# schematic.net
KiCad netlist of a schematic drawn in EAGLE
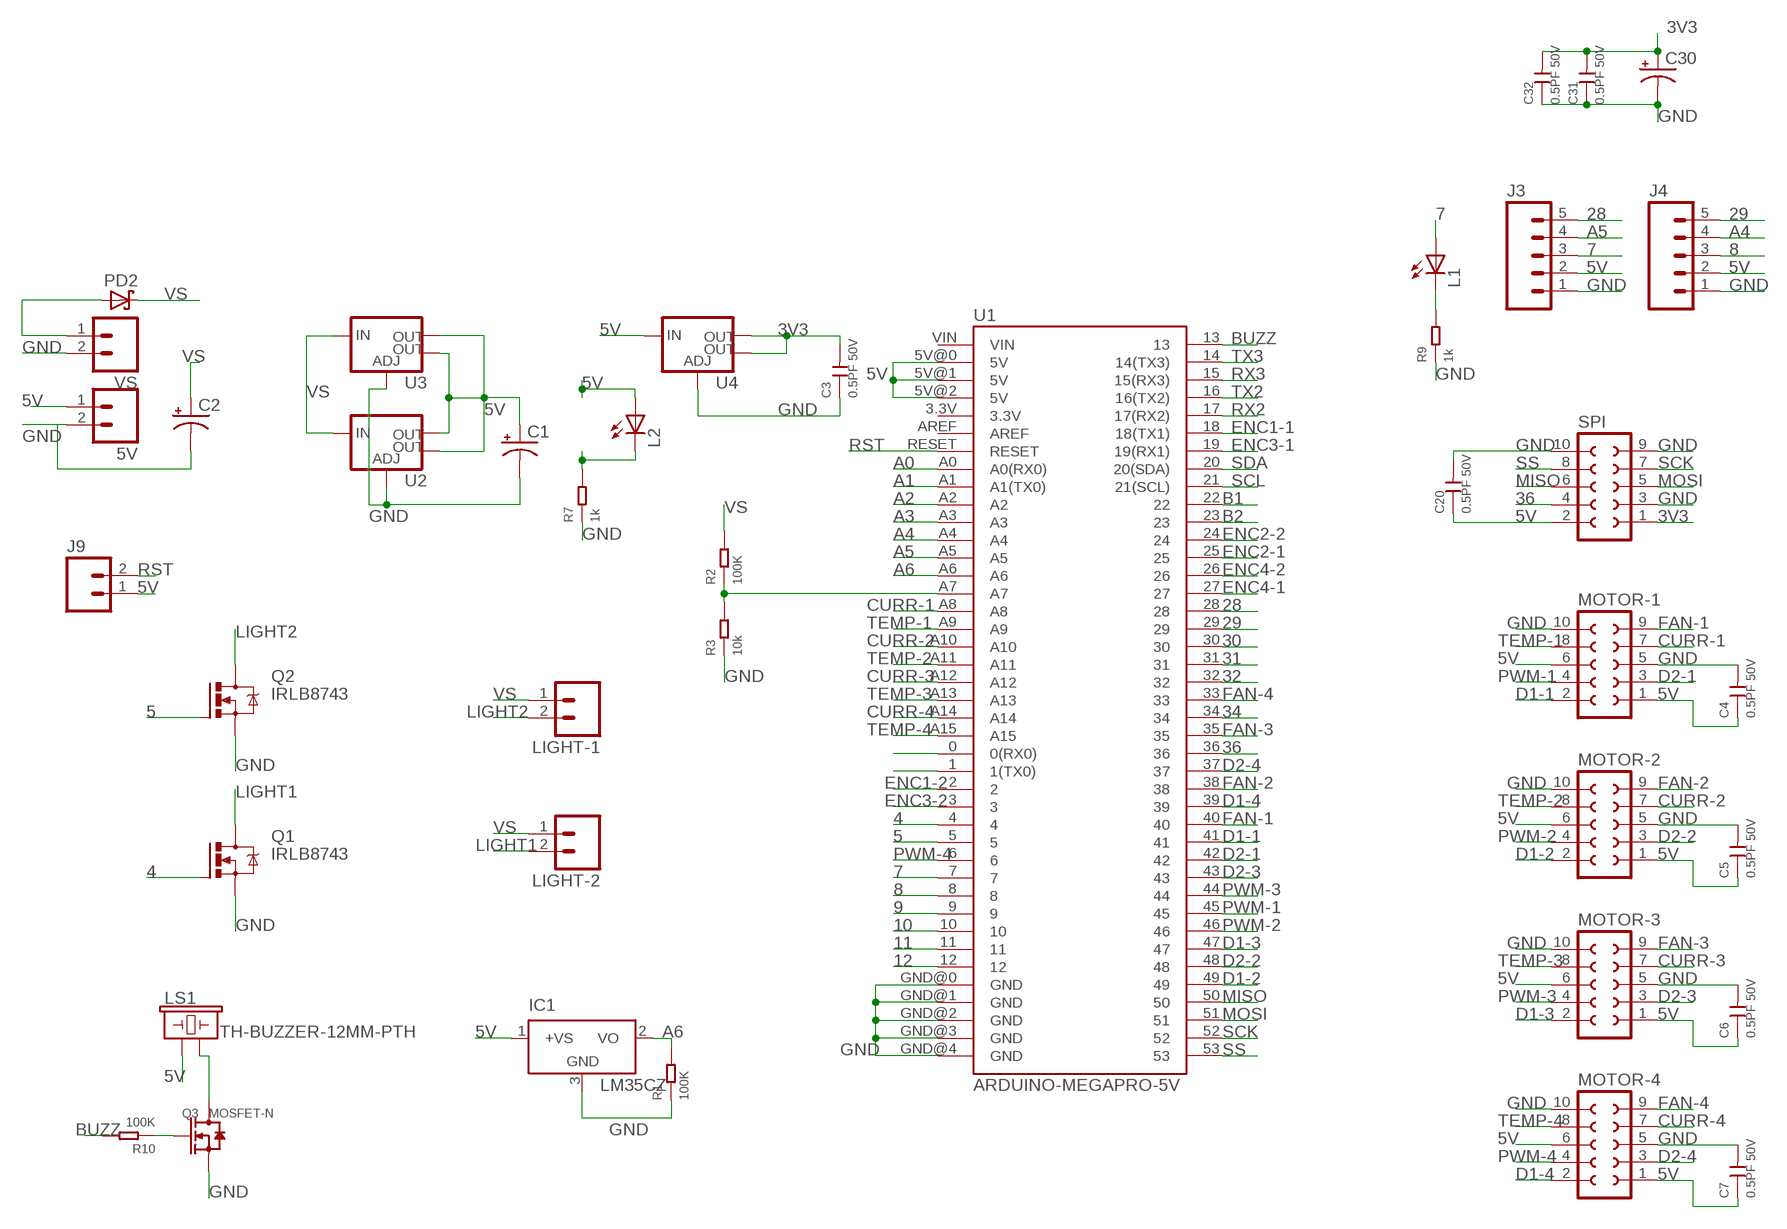
[diagram p0: schematic, sheet 1, part 1 of 2]
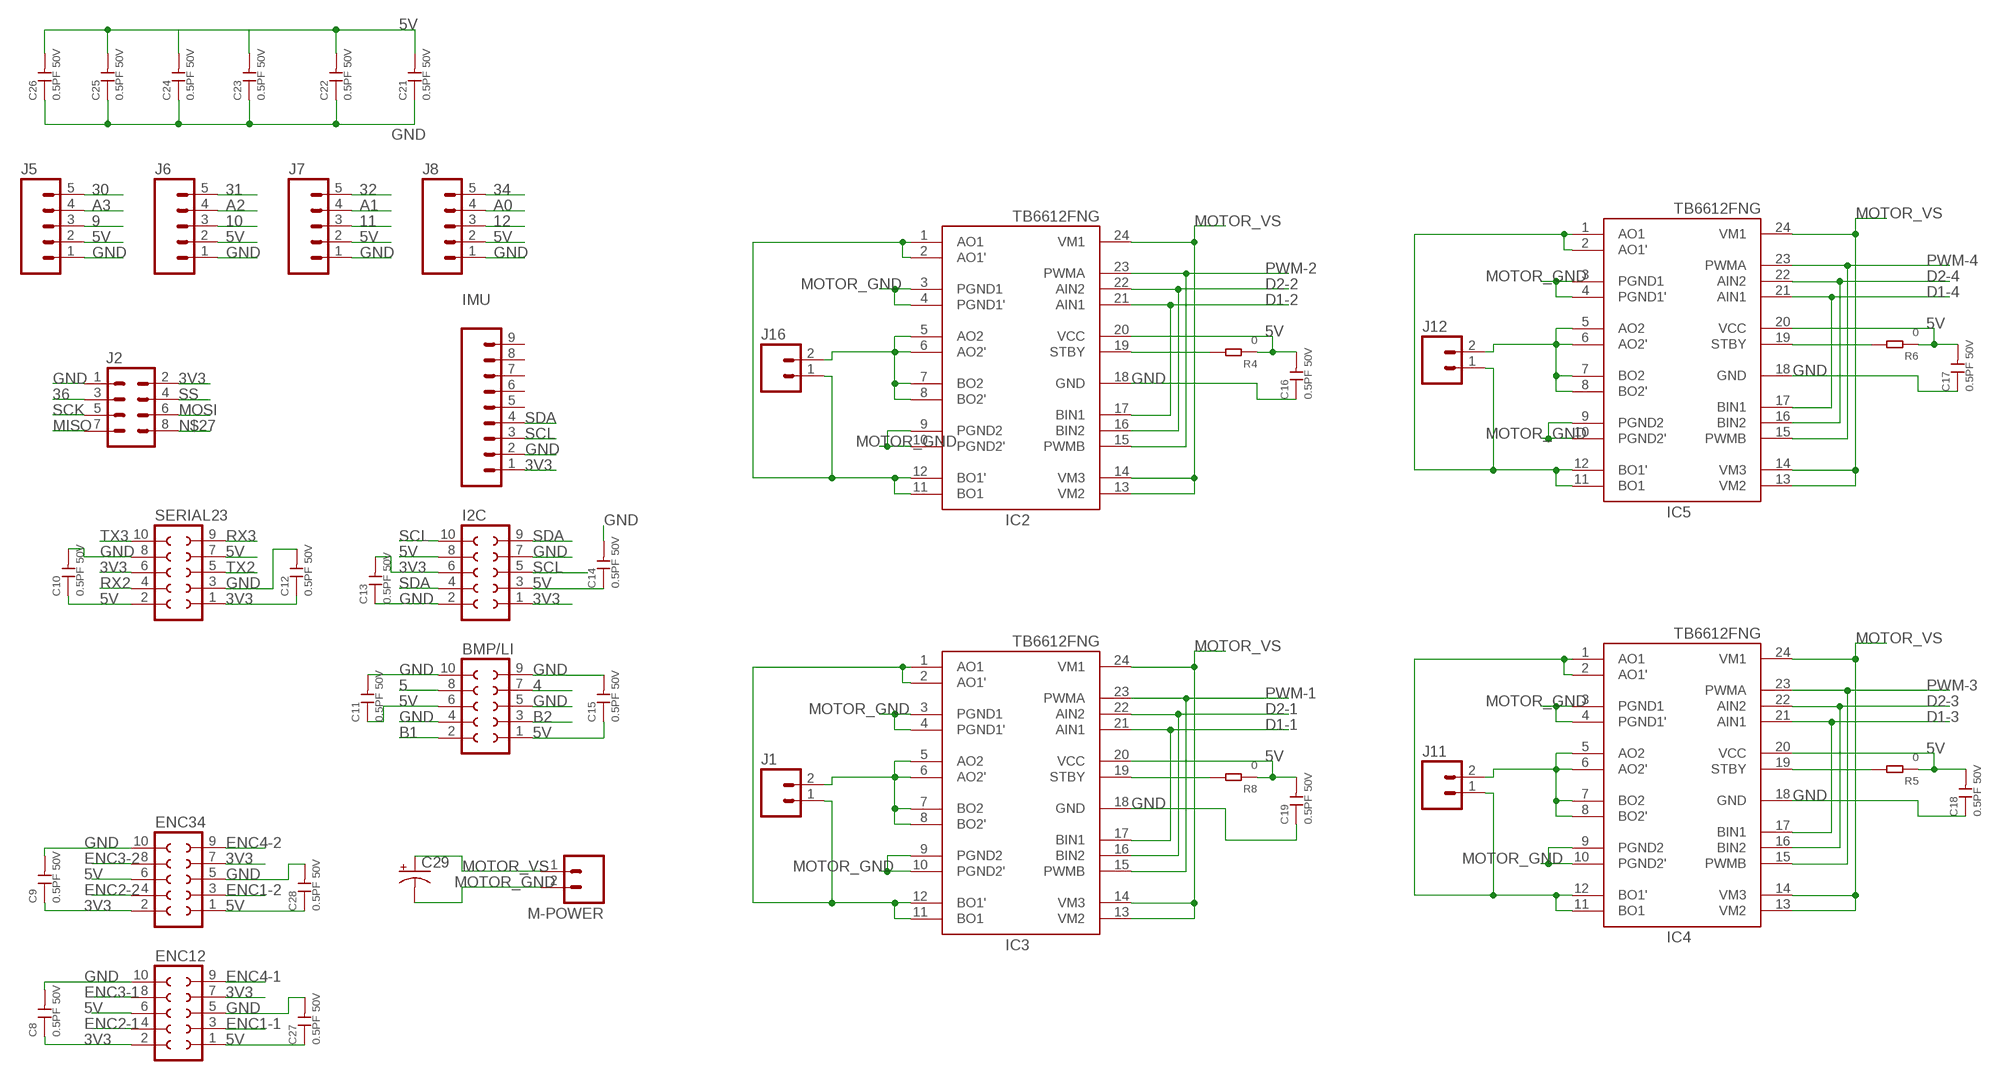
[diagram p1: schematic, sheet 1, part 2 of 2]

(export (version "E")
  (design (tool "Eeschema 10.0.6"))
  (components
    (comp (ref "5V")
      (value "M025MM")
      (footprint "eagle-import:SCREWTERMINAL-5MM-2")
      (libsource (lib "eagle-import") (part "M025MM"))
    )
    (comp (ref "BMP/LI")
      (value "SOCKET-10V")
      (footprint "eagle-import:S10V")
      (libsource (lib "eagle-import") (part "SOCKET-10V"))
    )
    (comp (ref "C1")
      (value "CAP_POLPTH1")
      (footprint "eagle-import:CPOL-RADIAL-100UF-25V")
      (libsource (lib "eagle-import") (part "CAP_POLPTH1"))
    )
    (comp (ref "C2")
      (value "CAP_POLPTH1")
      (footprint "eagle-import:CPOL-RADIAL-100UF-25V")
      (libsource (lib "eagle-import") (part "CAP_POLPTH1"))
    )
    (comp (ref "C3")
      (value "0.5PF 50V")
      (footprint "eagle-import:C0603")
      (libsource (lib "eagle-import") (part "CERAMIC-0.5PF-50V-0.1PF-NPO(0603)"))
    )
    (comp (ref "C4")
      (value "0.5PF 50V")
      (footprint "eagle-import:C0603")
      (libsource (lib "eagle-import") (part "CERAMIC-0.5PF-50V-0.1PF-NPO(0603)"))
    )
    (comp (ref "C5")
      (value "0.5PF 50V")
      (footprint "eagle-import:C0603")
      (libsource (lib "eagle-import") (part "CERAMIC-0.5PF-50V-0.1PF-NPO(0603)"))
    )
    (comp (ref "C6")
      (value "0.5PF 50V")
      (footprint "eagle-import:C0603")
      (libsource (lib "eagle-import") (part "CERAMIC-0.5PF-50V-0.1PF-NPO(0603)"))
    )
    (comp (ref "C7")
      (value "0.5PF 50V")
      (footprint "eagle-import:C0603")
      (libsource (lib "eagle-import") (part "CERAMIC-0.5PF-50V-0.1PF-NPO(0603)"))
    )
    (comp (ref "C8")
      (value "0.5PF 50V")
      (footprint "eagle-import:C0603")
      (libsource (lib "eagle-import") (part "CERAMIC-0.5PF-50V-0.1PF-NPO(0603)"))
    )
    (comp (ref "C9")
      (value "0.5PF 50V")
      (footprint "eagle-import:C0603")
      (libsource (lib "eagle-import") (part "CERAMIC-0.5PF-50V-0.1PF-NPO(0603)"))
    )
    (comp (ref "C10")
      (value "0.5PF 50V")
      (footprint "eagle-import:C0603")
      (libsource (lib "eagle-import") (part "CERAMIC-0.5PF-50V-0.1PF-NPO(0603)"))
    )
    (comp (ref "C11")
      (value "0.5PF 50V")
      (footprint "eagle-import:C0603")
      (libsource (lib "eagle-import") (part "CERAMIC-0.5PF-50V-0.1PF-NPO(0603)"))
    )
    (comp (ref "C12")
      (value "0.5PF 50V")
      (footprint "eagle-import:C0603")
      (libsource (lib "eagle-import") (part "CERAMIC-0.5PF-50V-0.1PF-NPO(0603)"))
    )
    (comp (ref "C13")
      (value "0.5PF 50V")
      (footprint "eagle-import:C0603")
      (libsource (lib "eagle-import") (part "CERAMIC-0.5PF-50V-0.1PF-NPO(0603)"))
    )
    (comp (ref "C14")
      (value "0.5PF 50V")
      (footprint "eagle-import:C0603")
      (libsource (lib "eagle-import") (part "CERAMIC-0.5PF-50V-0.1PF-NPO(0603)"))
    )
    (comp (ref "C15")
      (value "0.5PF 50V")
      (footprint "eagle-import:C0603")
      (libsource (lib "eagle-import") (part "CERAMIC-0.5PF-50V-0.1PF-NPO(0603)"))
    )
    (comp (ref "C16")
      (value "0.5PF 50V")
      (footprint "eagle-import:C0603")
      (libsource (lib "eagle-import") (part "CERAMIC-0.5PF-50V-0.1PF-NPO(0603)"))
    )
    (comp (ref "C17")
      (value "0.5PF 50V")
      (footprint "eagle-import:C0603")
      (libsource (lib "eagle-import") (part "CERAMIC-0.5PF-50V-0.1PF-NPO(0603)"))
    )
    (comp (ref "C18")
      (value "0.5PF 50V")
      (footprint "eagle-import:C0603")
      (libsource (lib "eagle-import") (part "CERAMIC-0.5PF-50V-0.1PF-NPO(0603)"))
    )
    (comp (ref "C19")
      (value "0.5PF 50V")
      (footprint "eagle-import:C0603")
      (libsource (lib "eagle-import") (part "CERAMIC-0.5PF-50V-0.1PF-NPO(0603)"))
    )
    (comp (ref "C20")
      (value "0.5PF 50V")
      (footprint "eagle-import:C0603")
      (libsource (lib "eagle-import") (part "CERAMIC-0.5PF-50V-0.1PF-NPO(0603)"))
    )
    (comp (ref "C21")
      (value "0.5PF 50V")
      (footprint "eagle-import:C0603")
      (libsource (lib "eagle-import") (part "CERAMIC-0.5PF-50V-0.1PF-NPO(0603)"))
    )
    (comp (ref "C22")
      (value "0.5PF 50V")
      (footprint "eagle-import:C0603")
      (libsource (lib "eagle-import") (part "CERAMIC-0.5PF-50V-0.1PF-NPO(0603)"))
    )
    (comp (ref "C23")
      (value "0.5PF 50V")
      (footprint "eagle-import:C0603")
      (libsource (lib "eagle-import") (part "CERAMIC-0.5PF-50V-0.1PF-NPO(0603)"))
    )
    (comp (ref "C24")
      (value "0.5PF 50V")
      (footprint "eagle-import:C0603")
      (libsource (lib "eagle-import") (part "CERAMIC-0.5PF-50V-0.1PF-NPO(0603)"))
    )
    (comp (ref "C25")
      (value "0.5PF 50V")
      (footprint "eagle-import:C0603")
      (libsource (lib "eagle-import") (part "CERAMIC-0.5PF-50V-0.1PF-NPO(0603)"))
    )
    (comp (ref "C26")
      (value "0.5PF 50V")
      (footprint "eagle-import:C0603")
      (libsource (lib "eagle-import") (part "CERAMIC-0.5PF-50V-0.1PF-NPO(0603)"))
    )
    (comp (ref "C27")
      (value "0.5PF 50V")
      (footprint "eagle-import:C0603")
      (libsource (lib "eagle-import") (part "CERAMIC-0.5PF-50V-0.1PF-NPO(0603)"))
    )
    (comp (ref "C28")
      (value "0.5PF 50V")
      (footprint "eagle-import:C0603")
      (libsource (lib "eagle-import") (part "CERAMIC-0.5PF-50V-0.1PF-NPO(0603)"))
    )
    (comp (ref "C29")
      (value "CAP_POLPTH1")
      (footprint "eagle-import:CPOL-RADIAL-100UF-25V")
      (libsource (lib "eagle-import") (part "CAP_POLPTH1"))
    )
    (comp (ref "C30")
      (value "CAP_POLPTH1")
      (footprint "eagle-import:CPOL-RADIAL-100UF-25V")
      (libsource (lib "eagle-import") (part "CAP_POLPTH1"))
    )
    (comp (ref "C31")
      (value "0.5PF 50V")
      (footprint "eagle-import:C0603")
      (libsource (lib "eagle-import") (part "CERAMIC-0.5PF-50V-0.1PF-NPO(0603)"))
    )
    (comp (ref "C32")
      (value "0.5PF 50V")
      (footprint "eagle-import:C0603")
      (libsource (lib "eagle-import") (part "CERAMIC-0.5PF-50V-0.1PF-NPO(0603)"))
    )
    (comp (ref "ENC12")
      (value "SOCKET-10V")
      (footprint "eagle-import:S10V")
      (libsource (lib "eagle-import") (part "SOCKET-10V"))
    )
    (comp (ref "ENC34")
      (value "SOCKET-10V")
      (footprint "eagle-import:S10V")
      (libsource (lib "eagle-import") (part "SOCKET-10V"))
    )
    (comp (ref "I2C")
      (value "SOCKET-10V")
      (footprint "eagle-import:S10V")
      (libsource (lib "eagle-import") (part "SOCKET-10V"))
    )
    (comp (ref "IC1")
      (value "LM35CZ")
      (footprint "eagle-import:TO92")
      (libsource (lib "eagle-import") (part "LM35CZ"))
    )
    (comp (ref "IC2")
      (value "TB6612FNG")
      (footprint "eagle-import:SSOP24")
      (libsource (lib "eagle-import") (part "TB6612FNG"))
    )
    (comp (ref "IC3")
      (value "TB6612FNG")
      (footprint "eagle-import:SSOP24")
      (libsource (lib "eagle-import") (part "TB6612FNG"))
    )
    (comp (ref "IC4")
      (value "TB6612FNG")
      (footprint "eagle-import:SSOP24")
      (libsource (lib "eagle-import") (part "TB6612FNG"))
    )
    (comp (ref "IC5")
      (value "TB6612FNG")
      (footprint "eagle-import:SSOP24")
      (libsource (lib "eagle-import") (part "TB6612FNG"))
    )
    (comp (ref "IMU")
      (value "M09")
      (footprint "eagle-import:1X09")
      (libsource (lib "eagle-import") (part "M09"))
    )
    (comp (ref "J1")
      (value "M025MM")
      (footprint "eagle-import:SCREWTERMINAL-5MM-2")
      (libsource (lib "eagle-import") (part "M025MM"))
    )
    (comp (ref "J2")
      (value "M04X2")
      (footprint "eagle-import:2X4")
      (libsource (lib "eagle-import") (part "M04X2"))
    )
    (comp (ref "J3")
      (value "M05PTH")
      (footprint "eagle-import:1X05")
      (libsource (lib "eagle-import") (part "M05PTH"))
    )
    (comp (ref "J4")
      (value "M05PTH")
      (footprint "eagle-import:1X05")
      (libsource (lib "eagle-import") (part "M05PTH"))
    )
    (comp (ref "J5")
      (value "M05PTH")
      (footprint "eagle-import:1X05")
      (libsource (lib "eagle-import") (part "M05PTH"))
    )
    (comp (ref "J6")
      (value "M05PTH")
      (footprint "eagle-import:1X05")
      (libsource (lib "eagle-import") (part "M05PTH"))
    )
    (comp (ref "J7")
      (value "M05PTH")
      (footprint "eagle-import:1X05")
      (libsource (lib "eagle-import") (part "M05PTH"))
    )
    (comp (ref "J8")
      (value "M05PTH")
      (footprint "eagle-import:1X05")
      (libsource (lib "eagle-import") (part "M05PTH"))
    )
    (comp (ref "J9")
      (value "M02PTH")
      (footprint "eagle-import:1X02")
      (libsource (lib "eagle-import") (part "M02PTH"))
    )
    (comp (ref "J11")
      (value "M025MM")
      (footprint "eagle-import:SCREWTERMINAL-5MM-2")
      (libsource (lib "eagle-import") (part "M025MM"))
    )
    (comp (ref "J12")
      (value "M025MM")
      (footprint "eagle-import:SCREWTERMINAL-5MM-2")
      (libsource (lib "eagle-import") (part "M025MM"))
    )
    (comp (ref "J16")
      (value "M025MM")
      (footprint "eagle-import:SCREWTERMINAL-5MM-2")
      (libsource (lib "eagle-import") (part "M025MM"))
    )
    (comp (ref "L1")
      (value "LEDCHIP-LED0603")
      (footprint "eagle-import:CHIP-LED0603")
      (libsource (lib "eagle-import") (part "LEDCHIP-LED0603"))
    )
    (comp (ref "L2")
      (value "LEDCHIP-LED0603")
      (footprint "eagle-import:CHIP-LED0603")
      (libsource (lib "eagle-import") (part "LEDCHIP-LED0603"))
    )
    (comp (ref "LIGHT-1")
      (value "M025MM")
      (footprint "eagle-import:SCREWTERMINAL-5MM-2")
      (libsource (lib "eagle-import") (part "M025MM"))
    )
    (comp (ref "LIGHT-2")
      (value "M025MM")
      (footprint "eagle-import:SCREWTERMINAL-5MM-2")
      (libsource (lib "eagle-import") (part "M025MM"))
    )
    (comp (ref "LS1")
      (value "TH-BUZZER-12MM-PTH")
      (footprint "eagle-import:BUZZER-12MM")
      (libsource (lib "eagle-import") (part "TH-BUZZER-12MM-PTH"))
    )
    (comp (ref "M-POWER")
      (value "M025MM")
      (footprint "eagle-import:SCREWTERMINAL-5MM-2")
      (libsource (lib "eagle-import") (part "M025MM"))
    )
    (comp (ref "MOTOR-1")
      (value "SOCKET-10V")
      (footprint "eagle-import:S10V")
      (libsource (lib "eagle-import") (part "SOCKET-10V"))
    )
    (comp (ref "MOTOR-2")
      (value "SOCKET-10V")
      (footprint "eagle-import:S10V")
      (libsource (lib "eagle-import") (part "SOCKET-10V"))
    )
    (comp (ref "MOTOR-3")
      (value "SOCKET-10V")
      (footprint "eagle-import:S10V")
      (libsource (lib "eagle-import") (part "SOCKET-10V"))
    )
    (comp (ref "MOTOR-4")
      (value "SOCKET-10V")
      (footprint "eagle-import:S10V")
      (libsource (lib "eagle-import") (part "SOCKET-10V"))
    )
    (comp (ref "PD2")
      (value "SCHOTTKY-DIODEF126Z12")
      (footprint "eagle-import:F126Z12")
      (libsource (lib "eagle-import") (part "SCHOTTKY-DIODEF126Z12"))
    )
    (comp (ref "Q1")
      (value "IRLB8743")
      (footprint "eagle-import:TO220BV")
      (libsource (lib "eagle-import") (part "IRF540"))
    )
    (comp (ref "Q2")
      (value "IRLB8743")
      (footprint "eagle-import:TO220BV")
      (libsource (lib "eagle-import") (part "IRF540"))
    )
    (comp (ref "Q3")
      (value "MOSFET-N")
      (footprint "eagle-import:SOT-23")
      (libsource (lib "eagle-import") (part "MOSFET-N"))
    )
    (comp (ref "R1")
      (value "100K")
      (footprint "eagle-import:R0603")
      (fields (field (name "MPN") "RC0603FR-071KL"))
      (libsource (lib "eagle-import") (part "SMD-RES-1K-1%-1/10W(0603)"))
    )
    (comp (ref "R2")
      (value "100K")
      (footprint "eagle-import:R0603")
      (fields (field (name "MPN") "RC0603FR-071KL"))
      (libsource (lib "eagle-import") (part "SMD-RES-1K-1%-1/10W(0603)"))
    )
    (comp (ref "R3")
      (value "10k")
      (footprint "eagle-import:R0603")
      (fields (field (name "MPN") "RC0603FR-071KL"))
      (libsource (lib "eagle-import") (part "SMD-RES-1K-1%-1/10W(0603)"))
    )
    (comp (ref "R4")
      (value "0")
      (footprint "eagle-import:R0603")
      (fields (field (name "MPN") "RC0603FR-071KL"))
      (libsource (lib "eagle-import") (part "SMD-RES-1K-1%-1/10W(0603)"))
    )
    (comp (ref "R5")
      (value "0")
      (footprint "eagle-import:R0603")
      (fields (field (name "MPN") "RC0603FR-071KL"))
      (libsource (lib "eagle-import") (part "SMD-RES-1K-1%-1/10W(0603)"))
    )
    (comp (ref "R6")
      (value "0")
      (footprint "eagle-import:R0603")
      (fields (field (name "MPN") "RC0603FR-071KL"))
      (libsource (lib "eagle-import") (part "SMD-RES-1K-1%-1/10W(0603)"))
    )
    (comp (ref "R7")
      (value "1k")
      (footprint "eagle-import:R0603")
      (fields (field (name "MPN") "RC0603FR-071KL"))
      (libsource (lib "eagle-import") (part "SMD-RES-1K-1%-1/10W(0603)"))
    )
    (comp (ref "R8")
      (value "0")
      (footprint "eagle-import:R0603")
      (fields (field (name "MPN") "RC0603FR-071KL"))
      (libsource (lib "eagle-import") (part "SMD-RES-1K-1%-1/10W(0603)"))
    )
    (comp (ref "R9")
      (value "1k")
      (footprint "eagle-import:R0603")
      (fields (field (name "MPN") "RC0603FR-071KL"))
      (libsource (lib "eagle-import") (part "SMD-RES-1K-1%-1/10W(0603)"))
    )
    (comp (ref "R10")
      (value "100K")
      (footprint "eagle-import:R0603")
      (fields (field (name "MPN") "RC0603FR-071KL"))
      (libsource (lib "eagle-import") (part "SMD-RES-1K-1%-1/10W(0603)"))
    )
    (comp (ref "SERIAL23")
      (value "SOCKET-10V")
      (footprint "eagle-import:S10V")
      (libsource (lib "eagle-import") (part "SOCKET-10V"))
    )
    (comp (ref "SPI")
      (value "SOCKET-10V")
      (footprint "eagle-import:S10V")
      (libsource (lib "eagle-import") (part "SOCKET-10V"))
    )
    (comp (ref "U1")
      (value "ARDUINO-MEGAPRO-5V")
      (footprint "eagle-import:ARDUINO_MEGA-PRO-5V")
      (libsource (lib "eagle-import") (part "ARDUINO-MEGAPRO-5V"))
    )
    (comp (ref "U2")
      (value "V_REG_LM1117SOT223")
      (footprint "eagle-import:SOT223")
      (libsource (lib "eagle-import") (part "V_REG_LM1117SOT223"))
    )
    (comp (ref "U3")
      (value "V_REG_LM1117SOT223")
      (footprint "eagle-import:SOT223")
      (libsource (lib "eagle-import") (part "V_REG_LM1117SOT223"))
    )
    (comp (ref "U4")
      (value "V_REG_LM1117SOT223")
      (footprint "eagle-import:SOT223")
      (libsource (lib "eagle-import") (part "V_REG_LM1117SOT223"))
    )
    (comp (ref "VS")
      (value "M025MM")
      (footprint "eagle-import:SCREWTERMINAL-5MM-2")
      (libsource (lib "eagle-import") (part "M025MM"))
    )
  )
  (nets
    (net (code "1") (name "/3V3") (class "Default")
      (node (ref "C12") (pin "1") (pinfunction "1_1") (pintype "passive"))
      (node (ref "C13") (pin "2") (pinfunction "2_2") (pintype "passive"))
      (node (ref "C3") (pin "2") (pinfunction "2_2") (pintype "passive"))
      (node (ref "C30") (pin "1") (pinfunction "+_1") (pintype "passive"))
      (node (ref "C31") (pin "2") (pinfunction "2_2") (pintype "passive"))
      (node (ref "C32") (pin "2") (pinfunction "2_2") (pintype "passive"))
      (node (ref "C8") (pin "1") (pinfunction "1_1") (pintype "passive"))
      (node (ref "C9") (pin "1") (pinfunction "1_1") (pintype "passive"))
      (node (ref "ENC12") (pin "2") (pinfunction "2_2") (pintype "passive"))
      (node (ref "ENC12") (pin "7") (pinfunction "7_7") (pintype "passive"))
      (node (ref "ENC34") (pin "2") (pinfunction "2_2") (pintype "passive"))
      (node (ref "ENC34") (pin "7") (pinfunction "7_7") (pintype "passive"))
      (node (ref "I2C") (pin "1") (pinfunction "1_1") (pintype "passive"))
      (node (ref "I2C") (pin "6") (pinfunction "6_6") (pintype "passive"))
      (node (ref "IMU") (pin "1") (pinfunction "1_1") (pintype "passive"))
      (node (ref "J2") (pin "2") (pinfunction "2_2") (pintype "passive"))
      (node (ref "SERIAL23") (pin "1") (pinfunction "1_1") (pintype "passive"))
      (node (ref "SERIAL23") (pin "6") (pinfunction "6_6") (pintype "passive"))
      (node (ref "SPI") (pin "1") (pinfunction "1_1") (pintype "passive"))
      (node (ref "U4") (pin "2") (pinfunction "OUT_2") (pintype "output"))
      (node (ref "U4") (pin "4") (pinfunction "OUT_4") (pintype "output"))
    )
    (net (code "2") (name "/4") (class "Default")
      (node (ref "BMP/LI") (pin "7") (pinfunction "7_7") (pintype "passive"))
      (node (ref "Q1") (pin "G") (pinfunction "G_G") (pintype "passive"))
      (node (ref "U1") (pin "4") (pinfunction "4_4") (pintype "bidirectional"))
    )
    (net (code "3") (name "/5") (class "Default")
      (node (ref "BMP/LI") (pin "8") (pinfunction "8_8") (pintype "passive"))
      (node (ref "Q2") (pin "G") (pinfunction "G_G") (pintype "passive"))
      (node (ref "U1") (pin "5") (pinfunction "5_5") (pintype "bidirectional"))
    )
    (net (code "4") (name "/5V") (class "Default")
      (node (ref "5V") (pin "1") (pinfunction "1_1") (pintype "passive"))
      (node (ref "BMP/LI") (pin "1") (pinfunction "1_1") (pintype "passive"))
      (node (ref "BMP/LI") (pin "6") (pinfunction "6_6") (pintype "passive"))
      (node (ref "C1") (pin "1") (pinfunction "+_1") (pintype "passive"))
      (node (ref "C10") (pin "1") (pinfunction "1_1") (pintype "passive"))
      (node (ref "C11") (pin "1") (pinfunction "1_1") (pintype "passive"))
      (node (ref "C14") (pin "1") (pinfunction "1_1") (pintype "passive"))
      (node (ref "C15") (pin "1") (pinfunction "1_1") (pintype "passive"))
      (node (ref "C16") (pin "2") (pinfunction "2_2") (pintype "passive"))
      (node (ref "C17") (pin "2") (pinfunction "2_2") (pintype "passive"))
      (node (ref "C18") (pin "2") (pinfunction "2_2") (pintype "passive"))
      (node (ref "C19") (pin "2") (pinfunction "2_2") (pintype "passive"))
      (node (ref "C20") (pin "1") (pinfunction "1_1") (pintype "passive"))
      (node (ref "C21") (pin "2") (pinfunction "2_2") (pintype "passive"))
      (node (ref "C22") (pin "2") (pinfunction "2_2") (pintype "passive"))
      (node (ref "C23") (pin "2") (pinfunction "2_2") (pintype "passive"))
      (node (ref "C24") (pin "2") (pinfunction "2_2") (pintype "passive"))
      (node (ref "C25") (pin "2") (pinfunction "2_2") (pintype "passive"))
      (node (ref "C26") (pin "2") (pinfunction "2_2") (pintype "passive"))
      (node (ref "C27") (pin "1") (pinfunction "1_1") (pintype "passive"))
      (node (ref "C28") (pin "1") (pinfunction "1_1") (pintype "passive"))
      (node (ref "C4") (pin "1") (pinfunction "1_1") (pintype "passive"))
      (node (ref "C5") (pin "1") (pinfunction "1_1") (pintype "passive"))
      (node (ref "C6") (pin "1") (pinfunction "1_1") (pintype "passive"))
      (node (ref "C7") (pin "1") (pinfunction "1_1") (pintype "passive"))
      (node (ref "ENC12") (pin "1") (pinfunction "1_1") (pintype "passive"))
      (node (ref "ENC12") (pin "6") (pinfunction "6_6") (pintype "passive"))
      (node (ref "ENC34") (pin "1") (pinfunction "1_1") (pintype "passive"))
      (node (ref "ENC34") (pin "6") (pinfunction "6_6") (pintype "passive"))
      (node (ref "I2C") (pin "3") (pinfunction "3_3") (pintype "passive"))
      (node (ref "I2C") (pin "8") (pinfunction "8_8") (pintype "passive"))
      (node (ref "IC1") (pin "1") (pinfunction "+VS_1") (pintype "input"))
      (node (ref "IC2") (pin "20") (pinfunction "VCC_20") (pintype "power_in"))
      (node (ref "IC3") (pin "20") (pinfunction "VCC_20") (pintype "power_in"))
      (node (ref "IC4") (pin "20") (pinfunction "VCC_20") (pintype "power_in"))
      (node (ref "IC5") (pin "20") (pinfunction "VCC_20") (pintype "power_in"))
      (node (ref "J3") (pin "2") (pinfunction "2_2") (pintype "passive"))
      (node (ref "J4") (pin "2") (pinfunction "2_2") (pintype "passive"))
      (node (ref "J5") (pin "2") (pinfunction "2_2") (pintype "passive"))
      (node (ref "J6") (pin "2") (pinfunction "2_2") (pintype "passive"))
      (node (ref "J7") (pin "2") (pinfunction "2_2") (pintype "passive"))
      (node (ref "J8") (pin "2") (pinfunction "2_2") (pintype "passive"))
      (node (ref "J9") (pin "1") (pinfunction "1_1") (pintype "passive"))
      (node (ref "L2") (pin "A") (pinfunction "A_A") (pintype "passive"))
      (node (ref "LS1") (pin "+") (pinfunction "1_+") (pintype "passive"))
      (node (ref "MOTOR-1") (pin "1") (pinfunction "1_1") (pintype "passive"))
      (node (ref "MOTOR-1") (pin "6") (pinfunction "6_6") (pintype "passive"))
      (node (ref "MOTOR-2") (pin "1") (pinfunction "1_1") (pintype "passive"))
      (node (ref "MOTOR-2") (pin "6") (pinfunction "6_6") (pintype "passive"))
      (node (ref "MOTOR-3") (pin "1") (pinfunction "1_1") (pintype "passive"))
      (node (ref "MOTOR-3") (pin "6") (pinfunction "6_6") (pintype "passive"))
      (node (ref "MOTOR-4") (pin "1") (pinfunction "1_1") (pintype "passive"))
      (node (ref "MOTOR-4") (pin "6") (pinfunction "6_6") (pintype "passive"))
      (node (ref "R4") (pin "1") (pinfunction "1_1") (pintype "passive"))
      (node (ref "R5") (pin "1") (pinfunction "1_1") (pintype "passive"))
      (node (ref "R6") (pin "1") (pinfunction "1_1") (pintype "passive"))
      (node (ref "R8") (pin "1") (pinfunction "1_1") (pintype "passive"))
      (node (ref "SERIAL23") (pin "2") (pinfunction "2_2") (pintype "passive"))
      (node (ref "SERIAL23") (pin "7") (pinfunction "7_7") (pintype "passive"))
      (node (ref "SPI") (pin "2") (pinfunction "2_2") (pintype "passive"))
      (node (ref "U1") (pin "5V@0") (pinfunction "5V_5V@0") (pintype "bidirectional"))
      (node (ref "U1") (pin "5V@1") (pinfunction "5V_5V@1") (pintype "bidirectional"))
      (node (ref "U1") (pin "5V@2") (pinfunction "5V_5V@2") (pintype "bidirectional"))
      (node (ref "U2") (pin "2") (pinfunction "OUT_2") (pintype "output"))
      (node (ref "U2") (pin "4") (pinfunction "OUT_4") (pintype "output"))
      (node (ref "U3") (pin "2") (pinfunction "OUT_2") (pintype "output"))
      (node (ref "U3") (pin "4") (pinfunction "OUT_4") (pintype "output"))
      (node (ref "U4") (pin "3") (pinfunction "IN_3") (pintype "input"))
    )
    (net (code "5") (name "/7") (class "Default")
      (node (ref "J3") (pin "3") (pinfunction "3_3") (pintype "passive"))
      (node (ref "L1") (pin "A") (pinfunction "A_A") (pintype "passive"))
      (node (ref "U1") (pin "7") (pinfunction "7_7") (pintype "bidirectional"))
    )
    (net (code "6") (name "/8") (class "Default")
      (node (ref "J4") (pin "3") (pinfunction "3_3") (pintype "passive"))
      (node (ref "U1") (pin "8") (pinfunction "8_8") (pintype "bidirectional"))
    )
    (net (code "7") (name "/9") (class "Default")
      (node (ref "J5") (pin "3") (pinfunction "3_3") (pintype "passive"))
      (node (ref "U1") (pin "9") (pinfunction "9_9") (pintype "bidirectional"))
    )
    (net (code "8") (name "/10") (class "Default")
      (node (ref "J6") (pin "3") (pinfunction "3_3") (pintype "passive"))
      (node (ref "U1") (pin "10") (pinfunction "10_10") (pintype "bidirectional"))
    )
    (net (code "9") (name "/11") (class "Default")
      (node (ref "J7") (pin "3") (pinfunction "3_3") (pintype "passive"))
      (node (ref "U1") (pin "11") (pinfunction "11_11") (pintype "bidirectional"))
    )
    (net (code "10") (name "/12") (class "Default")
      (node (ref "J8") (pin "3") (pinfunction "3_3") (pintype "passive"))
      (node (ref "U1") (pin "12") (pinfunction "12_12") (pintype "bidirectional"))
    )
    (net (code "11") (name "/28") (class "Default")
      (node (ref "J3") (pin "5") (pinfunction "5_5") (pintype "passive"))
      (node (ref "U1") (pin "28") (pinfunction "28_28") (pintype "bidirectional"))
    )
    (net (code "12") (name "/29") (class "Default")
      (node (ref "J4") (pin "5") (pinfunction "5_5") (pintype "passive"))
      (node (ref "U1") (pin "29") (pinfunction "29_29") (pintype "bidirectional"))
    )
    (net (code "13") (name "/30") (class "Default")
      (node (ref "J5") (pin "5") (pinfunction "5_5") (pintype "passive"))
      (node (ref "U1") (pin "30") (pinfunction "30_30") (pintype "bidirectional"))
    )
    (net (code "14") (name "/31") (class "Default")
      (node (ref "J6") (pin "5") (pinfunction "5_5") (pintype "passive"))
      (node (ref "U1") (pin "31") (pinfunction "31_31") (pintype "bidirectional"))
    )
    (net (code "15") (name "/32") (class "Default")
      (node (ref "J7") (pin "5") (pinfunction "5_5") (pintype "passive"))
      (node (ref "U1") (pin "32") (pinfunction "32_32") (pintype "bidirectional"))
    )
    (net (code "16") (name "/34") (class "Default")
      (node (ref "J8") (pin "5") (pinfunction "5_5") (pintype "passive"))
      (node (ref "U1") (pin "34") (pinfunction "34_34") (pintype "bidirectional"))
    )
    (net (code "17") (name "/36") (class "Default")
      (node (ref "J2") (pin "3") (pinfunction "3_3") (pintype "passive"))
      (node (ref "SPI") (pin "4") (pinfunction "4_4") (pintype "passive"))
      (node (ref "U1") (pin "36") (pinfunction "36_36") (pintype "bidirectional"))
    )
    (net (code "18") (name "/A0") (class "Default")
      (node (ref "J8") (pin "4") (pinfunction "4_4") (pintype "passive"))
      (node (ref "U1") (pin "A0") (pinfunction "A0(RX0)_A0") (pintype "bidirectional"))
    )
    (net (code "19") (name "/A1") (class "Default")
      (node (ref "J7") (pin "4") (pinfunction "4_4") (pintype "passive"))
      (node (ref "U1") (pin "A1") (pinfunction "A1(TX0)_A1") (pintype "bidirectional"))
    )
    (net (code "20") (name "/A2") (class "Default")
      (node (ref "J6") (pin "4") (pinfunction "4_4") (pintype "passive"))
      (node (ref "U1") (pin "A2") (pinfunction "A2_A2") (pintype "bidirectional"))
    )
    (net (code "21") (name "/A3") (class "Default")
      (node (ref "J5") (pin "4") (pinfunction "4_4") (pintype "passive"))
      (node (ref "U1") (pin "A3") (pinfunction "A3_A3") (pintype "bidirectional"))
    )
    (net (code "22") (name "/A4") (class "Default")
      (node (ref "J4") (pin "4") (pinfunction "4_4") (pintype "passive"))
      (node (ref "U1") (pin "A4") (pinfunction "A4_A4") (pintype "bidirectional"))
    )
    (net (code "23") (name "/A5") (class "Default")
      (node (ref "J3") (pin "4") (pinfunction "4_4") (pintype "passive"))
      (node (ref "U1") (pin "A5") (pinfunction "A5_A5") (pintype "bidirectional"))
    )
    (net (code "24") (name "/A6") (class "Default")
      (node (ref "IC1") (pin "2") (pinfunction "VO_2") (pintype "input"))
      (node (ref "R1") (pin "2") (pinfunction "2_2") (pintype "passive"))
      (node (ref "U1") (pin "A6") (pinfunction "A6_A6") (pintype "bidirectional"))
    )
    (net (code "25") (name "/B1") (class "Default")
      (node (ref "BMP/LI") (pin "2") (pinfunction "2_2") (pintype "passive"))
      (node (ref "U1") (pin "22") (pinfunction "22_22") (pintype "bidirectional"))
    )
    (net (code "26") (name "/B2") (class "Default")
      (node (ref "BMP/LI") (pin "3") (pinfunction "3_3") (pintype "passive"))
      (node (ref "U1") (pin "23") (pinfunction "23_23") (pintype "bidirectional"))
    )
    (net (code "27") (name "/BUZZ") (class "Default")
      (node (ref "R10") (pin "2") (pinfunction "2_2") (pintype "passive"))
      (node (ref "U1") (pin "13") (pinfunction "13_13") (pintype "bidirectional"))
    )
    (net (code "28") (name "/CURR-1") (class "Default")
      (node (ref "MOTOR-1") (pin "7") (pinfunction "7_7") (pintype "passive"))
      (node (ref "U1") (pin "A8") (pinfunction "A8_A8") (pintype "bidirectional"))
    )
    (net (code "29") (name "/CURR-2") (class "Default")
      (node (ref "MOTOR-2") (pin "7") (pinfunction "7_7") (pintype "passive"))
      (node (ref "U1") (pin "A10") (pinfunction "A10_A10") (pintype "bidirectional"))
    )
    (net (code "30") (name "/CURR-3") (class "Default")
      (node (ref "MOTOR-3") (pin "7") (pinfunction "7_7") (pintype "passive"))
      (node (ref "U1") (pin "A12") (pinfunction "A12_A12") (pintype "bidirectional"))
    )
    (net (code "31") (name "/CURR-4") (class "Default")
      (node (ref "MOTOR-4") (pin "7") (pinfunction "7_7") (pintype "passive"))
      (node (ref "U1") (pin "A14") (pinfunction "A14_A14") (pintype "bidirectional"))
    )
    (net (code "32") (name "/D1-1") (class "Default")
      (node (ref "IC3") (pin "17") (pinfunction "BIN1_17") (pintype "input"))
      (node (ref "IC3") (pin "21") (pinfunction "AIN1_21") (pintype "input"))
      (node (ref "MOTOR-1") (pin "2") (pinfunction "2_2") (pintype "passive"))
      (node (ref "U1") (pin "41") (pinfunction "41_41") (pintype "bidirectional"))
    )
    (net (code "33") (name "/D1-2") (class "Default")
      (node (ref "IC2") (pin "17") (pinfunction "BIN1_17") (pintype "input"))
      (node (ref "IC2") (pin "21") (pinfunction "AIN1_21") (pintype "input"))
      (node (ref "MOTOR-2") (pin "2") (pinfunction "2_2") (pintype "passive"))
      (node (ref "U1") (pin "49") (pinfunction "49_49") (pintype "bidirectional"))
    )
    (net (code "34") (name "/D1-3") (class "Default")
      (node (ref "IC4") (pin "17") (pinfunction "BIN1_17") (pintype "input"))
      (node (ref "IC4") (pin "21") (pinfunction "AIN1_21") (pintype "input"))
      (node (ref "MOTOR-3") (pin "2") (pinfunction "2_2") (pintype "passive"))
      (node (ref "U1") (pin "47") (pinfunction "47_47") (pintype "bidirectional"))
    )
    (net (code "35") (name "/D1-4") (class "Default")
      (node (ref "IC5") (pin "17") (pinfunction "BIN1_17") (pintype "input"))
      (node (ref "IC5") (pin "21") (pinfunction "AIN1_21") (pintype "input"))
      (node (ref "MOTOR-4") (pin "2") (pinfunction "2_2") (pintype "passive"))
      (node (ref "U1") (pin "39") (pinfunction "39_39") (pintype "bidirectional"))
    )
    (net (code "36") (name "/D2-1") (class "Default")
      (node (ref "IC3") (pin "16") (pinfunction "BIN2_16") (pintype "input"))
      (node (ref "IC3") (pin "22") (pinfunction "AIN2_22") (pintype "input"))
      (node (ref "MOTOR-1") (pin "3") (pinfunction "3_3") (pintype "passive"))
      (node (ref "U1") (pin "42") (pinfunction "42_42") (pintype "bidirectional"))
    )
    (net (code "37") (name "/D2-2") (class "Default")
      (node (ref "IC2") (pin "16") (pinfunction "BIN2_16") (pintype "input"))
      (node (ref "IC2") (pin "22") (pinfunction "AIN2_22") (pintype "input"))
      (node (ref "MOTOR-2") (pin "3") (pinfunction "3_3") (pintype "passive"))
      (node (ref "U1") (pin "48") (pinfunction "48_48") (pintype "bidirectional"))
    )
    (net (code "38") (name "/D2-3") (class "Default")
      (node (ref "IC4") (pin "16") (pinfunction "BIN2_16") (pintype "input"))
      (node (ref "IC4") (pin "22") (pinfunction "AIN2_22") (pintype "input"))
      (node (ref "MOTOR-3") (pin "3") (pinfunction "3_3") (pintype "passive"))
      (node (ref "U1") (pin "43") (pinfunction "43_43") (pintype "bidirectional"))
    )
    (net (code "39") (name "/D2-4") (class "Default")
      (node (ref "IC5") (pin "16") (pinfunction "BIN2_16") (pintype "input"))
      (node (ref "IC5") (pin "22") (pinfunction "AIN2_22") (pintype "input"))
      (node (ref "MOTOR-4") (pin "3") (pinfunction "3_3") (pintype "passive"))
      (node (ref "U1") (pin "37") (pinfunction "37_37") (pintype "bidirectional"))
    )
    (net (code "40") (name "/ENC1-1") (class "Default")
      (node (ref "ENC12") (pin "3") (pinfunction "3_3") (pintype "passive"))
      (node (ref "U1") (pin "18") (pinfunction "18(TX1)_18") (pintype "bidirectional"))
    )
    (net (code "41") (name "/ENC1-2") (class "Default")
      (node (ref "ENC34") (pin "3") (pinfunction "3_3") (pintype "passive"))
      (node (ref "U1") (pin "2") (pinfunction "2_2") (pintype "bidirectional"))
    )
    (net (code "42") (name "/ENC2-1") (class "Default")
      (node (ref "ENC12") (pin "4") (pinfunction "4_4") (pintype "passive"))
      (node (ref "U1") (pin "25") (pinfunction "25_25") (pintype "bidirectional"))
    )
    (net (code "43") (name "/ENC2-2") (class "Default")
      (node (ref "ENC34") (pin "4") (pinfunction "4_4") (pintype "passive"))
      (node (ref "U1") (pin "24") (pinfunction "24_24") (pintype "bidirectional"))
    )
    (net (code "44") (name "/ENC3-1") (class "Default")
      (node (ref "ENC12") (pin "8") (pinfunction "8_8") (pintype "passive"))
      (node (ref "U1") (pin "19") (pinfunction "19(RX1)_19") (pintype "bidirectional"))
    )
    (net (code "45") (name "/ENC3-2") (class "Default")
      (node (ref "ENC34") (pin "8") (pinfunction "8_8") (pintype "passive"))
      (node (ref "U1") (pin "3") (pinfunction "3_3") (pintype "bidirectional"))
    )
    (net (code "46") (name "/ENC4-1") (class "Default")
      (node (ref "ENC12") (pin "9") (pinfunction "9_9") (pintype "passive"))
      (node (ref "U1") (pin "27") (pinfunction "27_27") (pintype "bidirectional"))
    )
    (net (code "47") (name "/ENC4-2") (class "Default")
      (node (ref "ENC34") (pin "9") (pinfunction "9_9") (pintype "passive"))
      (node (ref "U1") (pin "26") (pinfunction "26_26") (pintype "bidirectional"))
    )
    (net (code "48") (name "/FAN-1") (class "Default")
      (node (ref "MOTOR-1") (pin "9") (pinfunction "9_9") (pintype "passive"))
      (node (ref "U1") (pin "40") (pinfunction "40_40") (pintype "bidirectional"))
    )
    (net (code "49") (name "/FAN-2") (class "Default")
      (node (ref "MOTOR-2") (pin "9") (pinfunction "9_9") (pintype "passive"))
      (node (ref "U1") (pin "38") (pinfunction "38_38") (pintype "bidirectional"))
    )
    (net (code "50") (name "/FAN-3") (class "Default")
      (node (ref "MOTOR-3") (pin "9") (pinfunction "9_9") (pintype "passive"))
      (node (ref "U1") (pin "35") (pinfunction "35_35") (pintype "bidirectional"))
    )
    (net (code "51") (name "/FAN-4") (class "Default")
      (node (ref "MOTOR-4") (pin "9") (pinfunction "9_9") (pintype "passive"))
      (node (ref "U1") (pin "33") (pinfunction "33_33") (pintype "bidirectional"))
    )
    (net (code "52") (name "/GND") (class "Default")
      (node (ref "5V") (pin "2") (pinfunction "2_2") (pintype "passive"))
      (node (ref "BMP/LI") (pin "10") (pinfunction "10_10") (pintype "passive"))
      (node (ref "BMP/LI") (pin "4") (pinfunction "4_4") (pintype "passive"))
      (node (ref "BMP/LI") (pin "5") (pinfunction "5_5") (pintype "passive"))
      (node (ref "BMP/LI") (pin "9") (pinfunction "9_9") (pintype "passive"))
      (node (ref "C1") (pin "2") (pinfunction "-_2") (pintype "passive"))
      (node (ref "C10") (pin "2") (pinfunction "2_2") (pintype "passive"))
      (node (ref "C11") (pin "2") (pinfunction "2_2") (pintype "passive"))
      (node (ref "C12") (pin "2") (pinfunction "2_2") (pintype "passive"))
      (node (ref "C13") (pin "1") (pinfunction "1_1") (pintype "passive"))
      (node (ref "C14") (pin "2") (pinfunction "2_2") (pintype "passive"))
      (node (ref "C15") (pin "2") (pinfunction "2_2") (pintype "passive"))
      (node (ref "C16") (pin "1") (pinfunction "1_1") (pintype "passive"))
      (node (ref "C17") (pin "1") (pinfunction "1_1") (pintype "passive"))
      (node (ref "C18") (pin "1") (pinfunction "1_1") (pintype "passive"))
      (node (ref "C19") (pin "1") (pinfunction "1_1") (pintype "passive"))
      (node (ref "C2") (pin "2") (pinfunction "-_2") (pintype "passive"))
      (node (ref "C20") (pin "2") (pinfunction "2_2") (pintype "passive"))
      (node (ref "C21") (pin "1") (pinfunction "1_1") (pintype "passive"))
      (node (ref "C22") (pin "1") (pinfunction "1_1") (pintype "passive"))
      (node (ref "C23") (pin "1") (pinfunction "1_1") (pintype "passive"))
      (node (ref "C24") (pin "1") (pinfunction "1_1") (pintype "passive"))
      (node (ref "C25") (pin "1") (pinfunction "1_1") (pintype "passive"))
      (node (ref "C26") (pin "1") (pinfunction "1_1") (pintype "passive"))
      (node (ref "C27") (pin "2") (pinfunction "2_2") (pintype "passive"))
      (node (ref "C28") (pin "2") (pinfunction "2_2") (pintype "passive"))
      (node (ref "C3") (pin "1") (pinfunction "1_1") (pintype "passive"))
      (node (ref "C30") (pin "2") (pinfunction "-_2") (pintype "passive"))
      (node (ref "C31") (pin "1") (pinfunction "1_1") (pintype "passive"))
      (node (ref "C32") (pin "1") (pinfunction "1_1") (pintype "passive"))
      (node (ref "C4") (pin "2") (pinfunction "2_2") (pintype "passive"))
      (node (ref "C5") (pin "2") (pinfunction "2_2") (pintype "passive"))
      (node (ref "C6") (pin "2") (pinfunction "2_2") (pintype "passive"))
      (node (ref "C7") (pin "2") (pinfunction "2_2") (pintype "passive"))
      (node (ref "C8") (pin "2") (pinfunction "2_2") (pintype "passive"))
      (node (ref "C9") (pin "2") (pinfunction "2_2") (pintype "passive"))
      (node (ref "ENC12") (pin "10") (pinfunction "10_10") (pintype "passive"))
      (node (ref "ENC12") (pin "5") (pinfunction "5_5") (pintype "passive"))
      (node (ref "ENC34") (pin "10") (pinfunction "10_10") (pintype "passive"))
      (node (ref "ENC34") (pin "5") (pinfunction "5_5") (pintype "passive"))
      (node (ref "I2C") (pin "2") (pinfunction "2_2") (pintype "passive"))
      (node (ref "I2C") (pin "7") (pinfunction "7_7") (pintype "passive"))
      (node (ref "IC1") (pin "3") (pinfunction "GND_3") (pintype "power_in"))
      (node (ref "IC2") (pin "18") (pinfunction "GND_18") (pintype "power_in"))
      (node (ref "IC3") (pin "18") (pinfunction "GND_18") (pintype "power_in"))
      (node (ref "IC4") (pin "18") (pinfunction "GND_18") (pintype "power_in"))
      (node (ref "IC5") (pin "18") (pinfunction "GND_18") (pintype "power_in"))
      (node (ref "IMU") (pin "2") (pinfunction "2_2") (pintype "passive"))
      (node (ref "J2") (pin "1") (pinfunction "1_1") (pintype "passive"))
      (node (ref "J3") (pin "1") (pinfunction "1_1") (pintype "passive"))
      (node (ref "J4") (pin "1") (pinfunction "1_1") (pintype "passive"))
      (node (ref "J5") (pin "1") (pinfunction "1_1") (pintype "passive"))
      (node (ref "J6") (pin "1") (pinfunction "1_1") (pintype "passive"))
      (node (ref "J7") (pin "1") (pinfunction "1_1") (pintype "passive"))
      (node (ref "J8") (pin "1") (pinfunction "1_1") (pintype "passive"))
      (node (ref "MOTOR-1") (pin "10") (pinfunction "10_10") (pintype "passive"))
      (node (ref "MOTOR-1") (pin "5") (pinfunction "5_5") (pintype "passive"))
      (node (ref "MOTOR-2") (pin "10") (pinfunction "10_10") (pintype "passive"))
      (node (ref "MOTOR-2") (pin "5") (pinfunction "5_5") (pintype "passive"))
      (node (ref "MOTOR-3") (pin "10") (pinfunction "10_10") (pintype "passive"))
      (node (ref "MOTOR-3") (pin "5") (pinfunction "5_5") (pintype "passive"))
      (node (ref "MOTOR-4") (pin "10") (pinfunction "10_10") (pintype "passive"))
      (node (ref "MOTOR-4") (pin "5") (pinfunction "5_5") (pintype "passive"))
      (node (ref "Q1") (pin "S") (pinfunction "S_S") (pintype "passive"))
      (node (ref "Q2") (pin "S") (pinfunction "S_S") (pintype "passive"))
      (node (ref "Q3") (pin "2") (pinfunction "S_2") (pintype "passive"))
      (node (ref "R1") (pin "1") (pinfunction "1_1") (pintype "passive"))
      (node (ref "R3") (pin "1") (pinfunction "1_1") (pintype "passive"))
      (node (ref "R7") (pin "1") (pinfunction "1_1") (pintype "passive"))
      (node (ref "R9") (pin "1") (pinfunction "1_1") (pintype "passive"))
      (node (ref "SERIAL23") (pin "3") (pinfunction "3_3") (pintype "passive"))
      (node (ref "SERIAL23") (pin "8") (pinfunction "8_8") (pintype "passive"))
      (node (ref "SPI") (pin "10") (pinfunction "10_10") (pintype "passive"))
      (node (ref "SPI") (pin "3") (pinfunction "3_3") (pintype "passive"))
      (node (ref "SPI") (pin "9") (pinfunction "9_9") (pintype "passive"))
      (node (ref "U1") (pin "GND@0") (pinfunction "GND_GND@0") (pintype "bidirectional"))
      (node (ref "U1") (pin "GND@1") (pinfunction "GND_GND@1") (pintype "bidirectional"))
      (node (ref "U1") (pin "GND@2") (pinfunction "GND_GND@2") (pintype "bidirectional"))
      (node (ref "U1") (pin "GND@3") (pinfunction "GND_GND@3") (pintype "bidirectional"))
      (node (ref "U1") (pin "GND@4") (pinfunction "GND_GND@4") (pintype "bidirectional"))
      (node (ref "U2") (pin "1") (pinfunction "ADJ_1") (pintype "input"))
      (node (ref "U3") (pin "1") (pinfunction "ADJ_1") (pintype "input"))
      (node (ref "U4") (pin "1") (pinfunction "ADJ_1") (pintype "input"))
      (node (ref "VS") (pin "2") (pinfunction "2_2") (pintype "passive"))
    )
    (net (code "53") (name "/LIGHT1") (class "Default")
      (node (ref "LIGHT-2") (pin "2") (pinfunction "2_2") (pintype "passive"))
      (node (ref "Q1") (pin "D") (pinfunction "D_D") (pintype "passive"))
    )
    (net (code "54") (name "/LIGHT2") (class "Default")
      (node (ref "LIGHT-1") (pin "2") (pinfunction "2_2") (pintype "passive"))
      (node (ref "Q2") (pin "D") (pinfunction "D_D") (pintype "passive"))
    )
    (net (code "55") (name "/MISO") (class "Default")
      (node (ref "J2") (pin "7") (pinfunction "7_7") (pintype "passive"))
      (node (ref "SPI") (pin "6") (pinfunction "6_6") (pintype "passive"))
      (node (ref "U1") (pin "50") (pinfunction "50_50") (pintype "bidirectional"))
    )
    (net (code "56") (name "/MOSI") (class "Default")
      (node (ref "J2") (pin "6") (pinfunction "6_6") (pintype "passive"))
      (node (ref "SPI") (pin "5") (pinfunction "5_5") (pintype "passive"))
      (node (ref "U1") (pin "51") (pinfunction "51_51") (pintype "bidirectional"))
    )
    (net (code "57") (name "/MOTOR_GND") (class "Default")
      (node (ref "C29") (pin "2") (pinfunction "-_2") (pintype "passive"))
      (node (ref "IC2") (pin "10") (pinfunction "PGND2'_10") (pintype "power_in"))
      (node (ref "IC2") (pin "3") (pinfunction "PGND1_3") (pintype "power_in"))
      (node (ref "IC2") (pin "4") (pinfunction "PGND1'_4") (pintype "power_in"))
      (node (ref "IC2") (pin "9") (pinfunction "PGND2_9") (pintype "power_in"))
      (node (ref "IC3") (pin "10") (pinfunction "PGND2'_10") (pintype "power_in"))
      (node (ref "IC3") (pin "3") (pinfunction "PGND1_3") (pintype "power_in"))
      (node (ref "IC3") (pin "4") (pinfunction "PGND1'_4") (pintype "power_in"))
      (node (ref "IC3") (pin "9") (pinfunction "PGND2_9") (pintype "power_in"))
      (node (ref "IC4") (pin "10") (pinfunction "PGND2'_10") (pintype "power_in"))
      (node (ref "IC4") (pin "3") (pinfunction "PGND1_3") (pintype "power_in"))
      (node (ref "IC4") (pin "4") (pinfunction "PGND1'_4") (pintype "power_in"))
      (node (ref "IC4") (pin "9") (pinfunction "PGND2_9") (pintype "power_in"))
      (node (ref "IC5") (pin "10") (pinfunction "PGND2'_10") (pintype "power_in"))
      (node (ref "IC5") (pin "3") (pinfunction "PGND1_3") (pintype "power_in"))
      (node (ref "IC5") (pin "4") (pinfunction "PGND1'_4") (pintype "power_in"))
      (node (ref "IC5") (pin "9") (pinfunction "PGND2_9") (pintype "power_in"))
      (node (ref "M-POWER") (pin "2") (pinfunction "2_2") (pintype "passive"))
    )
    (net (code "58") (name "/MOTOR_VS") (class "Default")
      (node (ref "C29") (pin "1") (pinfunction "+_1") (pintype "passive"))
      (node (ref "IC2") (pin "13") (pinfunction "VM2_13") (pintype "power_in"))
      (node (ref "IC2") (pin "14") (pinfunction "VM3_14") (pintype "power_in"))
      (node (ref "IC2") (pin "24") (pinfunction "VM1_24") (pintype "power_in"))
      (node (ref "IC3") (pin "13") (pinfunction "VM2_13") (pintype "power_in"))
      (node (ref "IC3") (pin "14") (pinfunction "VM3_14") (pintype "power_in"))
      (node (ref "IC3") (pin "24") (pinfunction "VM1_24") (pintype "power_in"))
      (node (ref "IC4") (pin "13") (pinfunction "VM2_13") (pintype "power_in"))
      (node (ref "IC4") (pin "14") (pinfunction "VM3_14") (pintype "power_in"))
      (node (ref "IC4") (pin "24") (pinfunction "VM1_24") (pintype "power_in"))
      (node (ref "IC5") (pin "13") (pinfunction "VM2_13") (pintype "power_in"))
      (node (ref "IC5") (pin "14") (pinfunction "VM3_14") (pintype "power_in"))
      (node (ref "IC5") (pin "24") (pinfunction "VM1_24") (pintype "power_in"))
      (node (ref "M-POWER") (pin "1") (pinfunction "1_1") (pintype "passive"))
    )
    (net (code "59") (name "/N$27") (class "Default")
      (node (ref "J2") (pin "8") (pinfunction "8_8") (pintype "passive"))
    )
    (net (code "60") (name "/PWM-1") (class "Default")
      (node (ref "IC3") (pin "15") (pinfunction "PWMB_15") (pintype "input"))
      (node (ref "IC3") (pin "23") (pinfunction "PWMA_23") (pintype "input"))
      (node (ref "MOTOR-1") (pin "4") (pinfunction "4_4") (pintype "passive"))
      (node (ref "U1") (pin "45") (pinfunction "45_45") (pintype "bidirectional"))
    )
    (net (code "61") (name "/PWM-2") (class "Default")
      (node (ref "IC2") (pin "15") (pinfunction "PWMB_15") (pintype "input"))
      (node (ref "IC2") (pin "23") (pinfunction "PWMA_23") (pintype "input"))
      (node (ref "MOTOR-2") (pin "4") (pinfunction "4_4") (pintype "passive"))
      (node (ref "U1") (pin "46") (pinfunction "46_46") (pintype "bidirectional"))
    )
    (net (code "62") (name "/PWM-3") (class "Default")
      (node (ref "IC4") (pin "15") (pinfunction "PWMB_15") (pintype "input"))
      (node (ref "IC4") (pin "23") (pinfunction "PWMA_23") (pintype "input"))
      (node (ref "MOTOR-3") (pin "4") (pinfunction "4_4") (pintype "passive"))
      (node (ref "U1") (pin "44") (pinfunction "44_44") (pintype "bidirectional"))
    )
    (net (code "63") (name "/PWM-4") (class "Default")
      (node (ref "IC5") (pin "15") (pinfunction "PWMB_15") (pintype "input"))
      (node (ref "IC5") (pin "23") (pinfunction "PWMA_23") (pintype "input"))
      (node (ref "MOTOR-4") (pin "4") (pinfunction "4_4") (pintype "passive"))
      (node (ref "U1") (pin "6") (pinfunction "6_6") (pintype "bidirectional"))
    )
    (net (code "64") (name "/RST") (class "Default")
      (node (ref "J9") (pin "2") (pinfunction "2_2") (pintype "passive"))
      (node (ref "U1") (pin "RESET") (pinfunction "RESET_RESET") (pintype "bidirectional"))
    )
    (net (code "65") (name "/RX2") (class "Default")
      (node (ref "SERIAL23") (pin "4") (pinfunction "4_4") (pintype "passive"))
      (node (ref "U1") (pin "17") (pinfunction "17(RX2)_17") (pintype "bidirectional"))
    )
    (net (code "66") (name "/RX3") (class "Default")
      (node (ref "SERIAL23") (pin "9") (pinfunction "9_9") (pintype "passive"))
      (node (ref "U1") (pin "15") (pinfunction "15(RX3)_15") (pintype "bidirectional"))
    )
    (net (code "67") (name "/SCK") (class "Default")
      (node (ref "J2") (pin "5") (pinfunction "5_5") (pintype "passive"))
      (node (ref "SPI") (pin "7") (pinfunction "7_7") (pintype "passive"))
      (node (ref "U1") (pin "52") (pinfunction "52_52") (pintype "bidirectional"))
    )
    (net (code "68") (name "/SCL") (class "Default")
      (node (ref "I2C") (pin "10") (pinfunction "10_10") (pintype "passive"))
      (node (ref "I2C") (pin "5") (pinfunction "5_5") (pintype "passive"))
      (node (ref "IMU") (pin "3") (pinfunction "3_3") (pintype "passive"))
      (node (ref "U1") (pin "21") (pinfunction "21(SCL)_21") (pintype "bidirectional"))
    )
    (net (code "69") (name "/SDA") (class "Default")
      (node (ref "I2C") (pin "4") (pinfunction "4_4") (pintype "passive"))
      (node (ref "I2C") (pin "9") (pinfunction "9_9") (pintype "passive"))
      (node (ref "IMU") (pin "4") (pinfunction "4_4") (pintype "passive"))
      (node (ref "U1") (pin "20") (pinfunction "20(SDA)_20") (pintype "bidirectional"))
    )
    (net (code "70") (name "/SS") (class "Default")
      (node (ref "J2") (pin "4") (pinfunction "4_4") (pintype "passive"))
      (node (ref "SPI") (pin "8") (pinfunction "8_8") (pintype "passive"))
      (node (ref "U1") (pin "53") (pinfunction "53_53") (pintype "bidirectional"))
    )
    (net (code "71") (name "/TEMP-1") (class "Default")
      (node (ref "MOTOR-1") (pin "8") (pinfunction "8_8") (pintype "passive"))
      (node (ref "U1") (pin "A9") (pinfunction "A9_A9") (pintype "bidirectional"))
    )
    (net (code "72") (name "/TEMP-2") (class "Default")
      (node (ref "MOTOR-2") (pin "8") (pinfunction "8_8") (pintype "passive"))
      (node (ref "U1") (pin "A11") (pinfunction "A11_A11") (pintype "bidirectional"))
    )
    (net (code "73") (name "/TEMP-3") (class "Default")
      (node (ref "MOTOR-3") (pin "8") (pinfunction "8_8") (pintype "passive"))
      (node (ref "U1") (pin "A13") (pinfunction "A13_A13") (pintype "bidirectional"))
    )
    (net (code "74") (name "/TEMP-4") (class "Default")
      (node (ref "MOTOR-4") (pin "8") (pinfunction "8_8") (pintype "passive"))
      (node (ref "U1") (pin "A15") (pinfunction "A15_A15") (pintype "bidirectional"))
    )
    (net (code "75") (name "/TX2") (class "Default")
      (node (ref "SERIAL23") (pin "5") (pinfunction "5_5") (pintype "passive"))
      (node (ref "U1") (pin "16") (pinfunction "16(TX2)_16") (pintype "bidirectional"))
    )
    (net (code "76") (name "/TX3") (class "Default")
      (node (ref "SERIAL23") (pin "10") (pinfunction "10_10") (pintype "passive"))
      (node (ref "U1") (pin "14") (pinfunction "14(TX3)_14") (pintype "bidirectional"))
    )
    (net (code "77") (name "/VS") (class "Default")
      (node (ref "C2") (pin "1") (pinfunction "+_1") (pintype "passive"))
      (node (ref "LIGHT-1") (pin "1") (pinfunction "1_1") (pintype "passive"))
      (node (ref "LIGHT-2") (pin "1") (pinfunction "1_1") (pintype "passive"))
      (node (ref "PD2") (pin "C") (pinfunction "C_C") (pintype "passive"))
      (node (ref "R2") (pin "2") (pinfunction "2_2") (pintype "passive"))
      (node (ref "U2") (pin "3") (pinfunction "IN_3") (pintype "input"))
      (node (ref "U3") (pin "3") (pinfunction "IN_3") (pintype "input"))
    )
    (net (code "78") (name "Net-(IC2-AO1')") (class "Default")
      (node (ref "IC2") (pin "1") (pinfunction "AO1_1") (pintype "output"))
      (node (ref "IC2") (pin "11") (pinfunction "BO1_11") (pintype "output"))
      (node (ref "IC2") (pin "12") (pinfunction "BO1'_12") (pintype "output"))
      (node (ref "IC2") (pin "2") (pinfunction "AO1'_2") (pintype "output"))
      (node (ref "J16") (pin "1") (pinfunction "1_1") (pintype "passive"))
    )
    (net (code "79") (name "Net-(IC2-AO2')") (class "Default")
      (node (ref "IC2") (pin "5") (pinfunction "AO2_5") (pintype "output"))
      (node (ref "IC2") (pin "6") (pinfunction "AO2'_6") (pintype "output"))
      (node (ref "IC2") (pin "7") (pinfunction "BO2_7") (pintype "output"))
      (node (ref "IC2") (pin "8") (pinfunction "BO2'_8") (pintype "output"))
      (node (ref "J16") (pin "2") (pinfunction "2_2") (pintype "passive"))
    )
    (net (code "80") (name "Net-(IC2-STBY)") (class "Default")
      (node (ref "IC2") (pin "19") (pinfunction "STBY_19") (pintype "input"))
      (node (ref "R4") (pin "2") (pinfunction "2_2") (pintype "passive"))
    )
    (net (code "81") (name "Net-(IC3-AO1')") (class "Default")
      (node (ref "IC3") (pin "1") (pinfunction "AO1_1") (pintype "output"))
      (node (ref "IC3") (pin "11") (pinfunction "BO1_11") (pintype "output"))
      (node (ref "IC3") (pin "12") (pinfunction "BO1'_12") (pintype "output"))
      (node (ref "IC3") (pin "2") (pinfunction "AO1'_2") (pintype "output"))
      (node (ref "J1") (pin "1") (pinfunction "1_1") (pintype "passive"))
    )
    (net (code "82") (name "Net-(IC3-AO2')") (class "Default")
      (node (ref "IC3") (pin "5") (pinfunction "AO2_5") (pintype "output"))
      (node (ref "IC3") (pin "6") (pinfunction "AO2'_6") (pintype "output"))
      (node (ref "IC3") (pin "7") (pinfunction "BO2_7") (pintype "output"))
      (node (ref "IC3") (pin "8") (pinfunction "BO2'_8") (pintype "output"))
      (node (ref "J1") (pin "2") (pinfunction "2_2") (pintype "passive"))
    )
    (net (code "83") (name "Net-(IC3-STBY)") (class "Default")
      (node (ref "IC3") (pin "19") (pinfunction "STBY_19") (pintype "input"))
      (node (ref "R8") (pin "2") (pinfunction "2_2") (pintype "passive"))
    )
    (net (code "84") (name "Net-(IC4-AO1')") (class "Default")
      (node (ref "IC4") (pin "1") (pinfunction "AO1_1") (pintype "output"))
      (node (ref "IC4") (pin "11") (pinfunction "BO1_11") (pintype "output"))
      (node (ref "IC4") (pin "12") (pinfunction "BO1'_12") (pintype "output"))
      (node (ref "IC4") (pin "2") (pinfunction "AO1'_2") (pintype "output"))
      (node (ref "J11") (pin "1") (pinfunction "1_1") (pintype "passive"))
    )
    (net (code "85") (name "Net-(IC4-AO2')") (class "Default")
      (node (ref "IC4") (pin "5") (pinfunction "AO2_5") (pintype "output"))
      (node (ref "IC4") (pin "6") (pinfunction "AO2'_6") (pintype "output"))
      (node (ref "IC4") (pin "7") (pinfunction "BO2_7") (pintype "output"))
      (node (ref "IC4") (pin "8") (pinfunction "BO2'_8") (pintype "output"))
      (node (ref "J11") (pin "2") (pinfunction "2_2") (pintype "passive"))
    )
    (net (code "86") (name "Net-(IC4-STBY)") (class "Default")
      (node (ref "IC4") (pin "19") (pinfunction "STBY_19") (pintype "input"))
      (node (ref "R5") (pin "2") (pinfunction "2_2") (pintype "passive"))
    )
    (net (code "87") (name "Net-(IC5-AO1')") (class "Default")
      (node (ref "IC5") (pin "1") (pinfunction "AO1_1") (pintype "output"))
      (node (ref "IC5") (pin "11") (pinfunction "BO1_11") (pintype "output"))
      (node (ref "IC5") (pin "12") (pinfunction "BO1'_12") (pintype "output"))
      (node (ref "IC5") (pin "2") (pinfunction "AO1'_2") (pintype "output"))
      (node (ref "J12") (pin "1") (pinfunction "1_1") (pintype "passive"))
    )
    (net (code "88") (name "Net-(IC5-AO2')") (class "Default")
      (node (ref "IC5") (pin "5") (pinfunction "AO2_5") (pintype "output"))
      (node (ref "IC5") (pin "6") (pinfunction "AO2'_6") (pintype "output"))
      (node (ref "IC5") (pin "7") (pinfunction "BO2_7") (pintype "output"))
      (node (ref "IC5") (pin "8") (pinfunction "BO2'_8") (pintype "output"))
      (node (ref "J12") (pin "2") (pinfunction "2_2") (pintype "passive"))
    )
    (net (code "89") (name "Net-(IC5-STBY)") (class "Default")
      (node (ref "IC5") (pin "19") (pinfunction "STBY_19") (pintype "input"))
      (node (ref "R6") (pin "2") (pinfunction "2_2") (pintype "passive"))
    )
    (net (code "90") (name "Net-(L1-PadC)") (class "Default")
      (node (ref "L1") (pin "C") (pinfunction "C_C") (pintype "passive"))
      (node (ref "R9") (pin "2") (pinfunction "2_2") (pintype "passive"))
    )
    (net (code "91") (name "Net-(L2-PadC)") (class "Default")
      (node (ref "L2") (pin "C") (pinfunction "C_C") (pintype "passive"))
      (node (ref "R7") (pin "2") (pinfunction "2_2") (pintype "passive"))
    )
    (net (code "92") (name "Net-(LS1-2)") (class "Default")
      (node (ref "LS1") (pin "-") (pinfunction "2_-") (pintype "passive"))
      (node (ref "Q3") (pin "3") (pinfunction "D_3") (pintype "passive"))
    )
    (net (code "93") (name "Net-(PD2-PadA)") (class "Default")
      (node (ref "PD2") (pin "A") (pinfunction "A_A") (pintype "passive"))
      (node (ref "VS") (pin "1") (pinfunction "1_1") (pintype "passive"))
    )
    (net (code "94") (name "Net-(Q3-G)") (class "Default")
      (node (ref "Q3") (pin "1") (pinfunction "G_1") (pintype "passive"))
      (node (ref "R10") (pin "1") (pinfunction "1_1") (pintype "passive"))
    )
    (net (code "95") (name "Net-(R2-Pad1)") (class "Default")
      (node (ref "R2") (pin "1") (pinfunction "1_1") (pintype "passive"))
      (node (ref "R3") (pin "2") (pinfunction "2_2") (pintype "passive"))
      (node (ref "U1") (pin "A7") (pinfunction "A7_A7") (pintype "bidirectional"))
    )
    (net (code "96") (name "unconnected-(IMU-Pad5)") (class "Default")
      (node (ref "IMU") (pin "5") (pinfunction "5_5") (pintype "passive"))
    )
    (net (code "97") (name "unconnected-(IMU-Pad6)") (class "Default")
      (node (ref "IMU") (pin "6") (pinfunction "6_6") (pintype "passive"))
    )
    (net (code "98") (name "unconnected-(IMU-Pad7)") (class "Default")
      (node (ref "IMU") (pin "7") (pinfunction "7_7") (pintype "passive"))
    )
    (net (code "99") (name "unconnected-(IMU-Pad8)") (class "Default")
      (node (ref "IMU") (pin "8") (pinfunction "8_8") (pintype "passive"))
    )
    (net (code "100") (name "unconnected-(IMU-Pad9)") (class "Default")
      (node (ref "IMU") (pin "9") (pinfunction "9_9") (pintype "passive"))
    )
    (net (code "101") (name "unconnected-(U1-0(RX0)-Pad0)") (class "Default")
      (node (ref "U1") (pin "0") (pinfunction "0(RX0)_0") (pintype "bidirectional"))
    )
    (net (code "102") (name "unconnected-(U1-1(TX0)-Pad1)") (class "Default")
      (node (ref "U1") (pin "1") (pinfunction "1(TX0)_1") (pintype "bidirectional"))
    )
    (net (code "103") (name "unconnected-(U1-Pad3.3V)") (class "Default")
      (node (ref "U1") (pin "3.3V") (pinfunction "3.3V_3.3V") (pintype "bidirectional"))
    )
    (net (code "104") (name "unconnected-(U1-PadAREF)") (class "Default")
      (node (ref "U1") (pin "AREF") (pinfunction "AREF_AREF") (pintype "bidirectional"))
    )
    (net (code "105") (name "unconnected-(U1-PadVIN)") (class "Default")
      (node (ref "U1") (pin "VIN") (pinfunction "VIN_VIN") (pintype "bidirectional"))
    )
  )
)
